# MLX81310EVB_BoardHolder.net
KiCad netlist of a schematic drawn in EAGLE
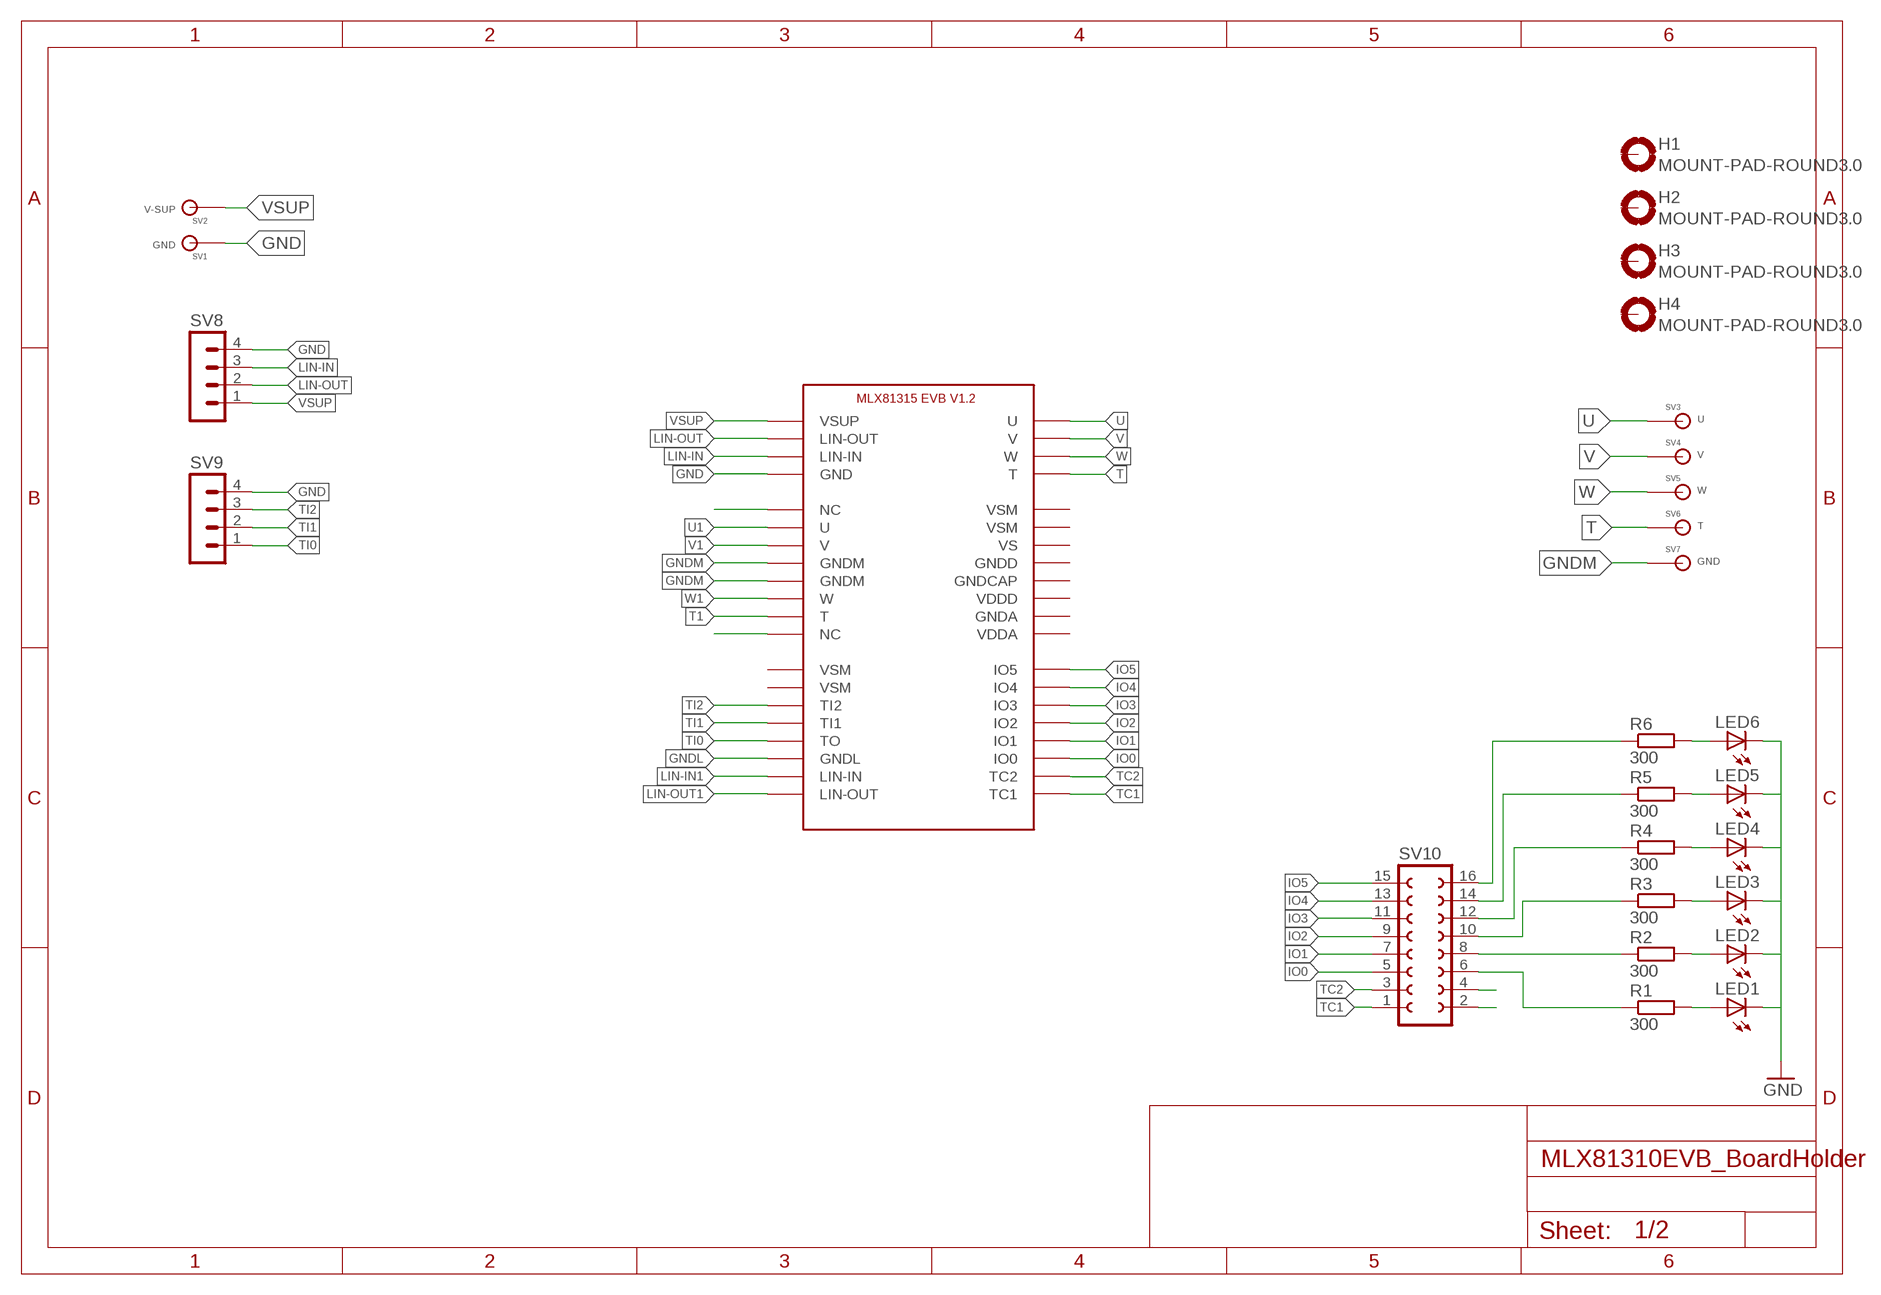
[diagram p0: schematic, sheet 1]
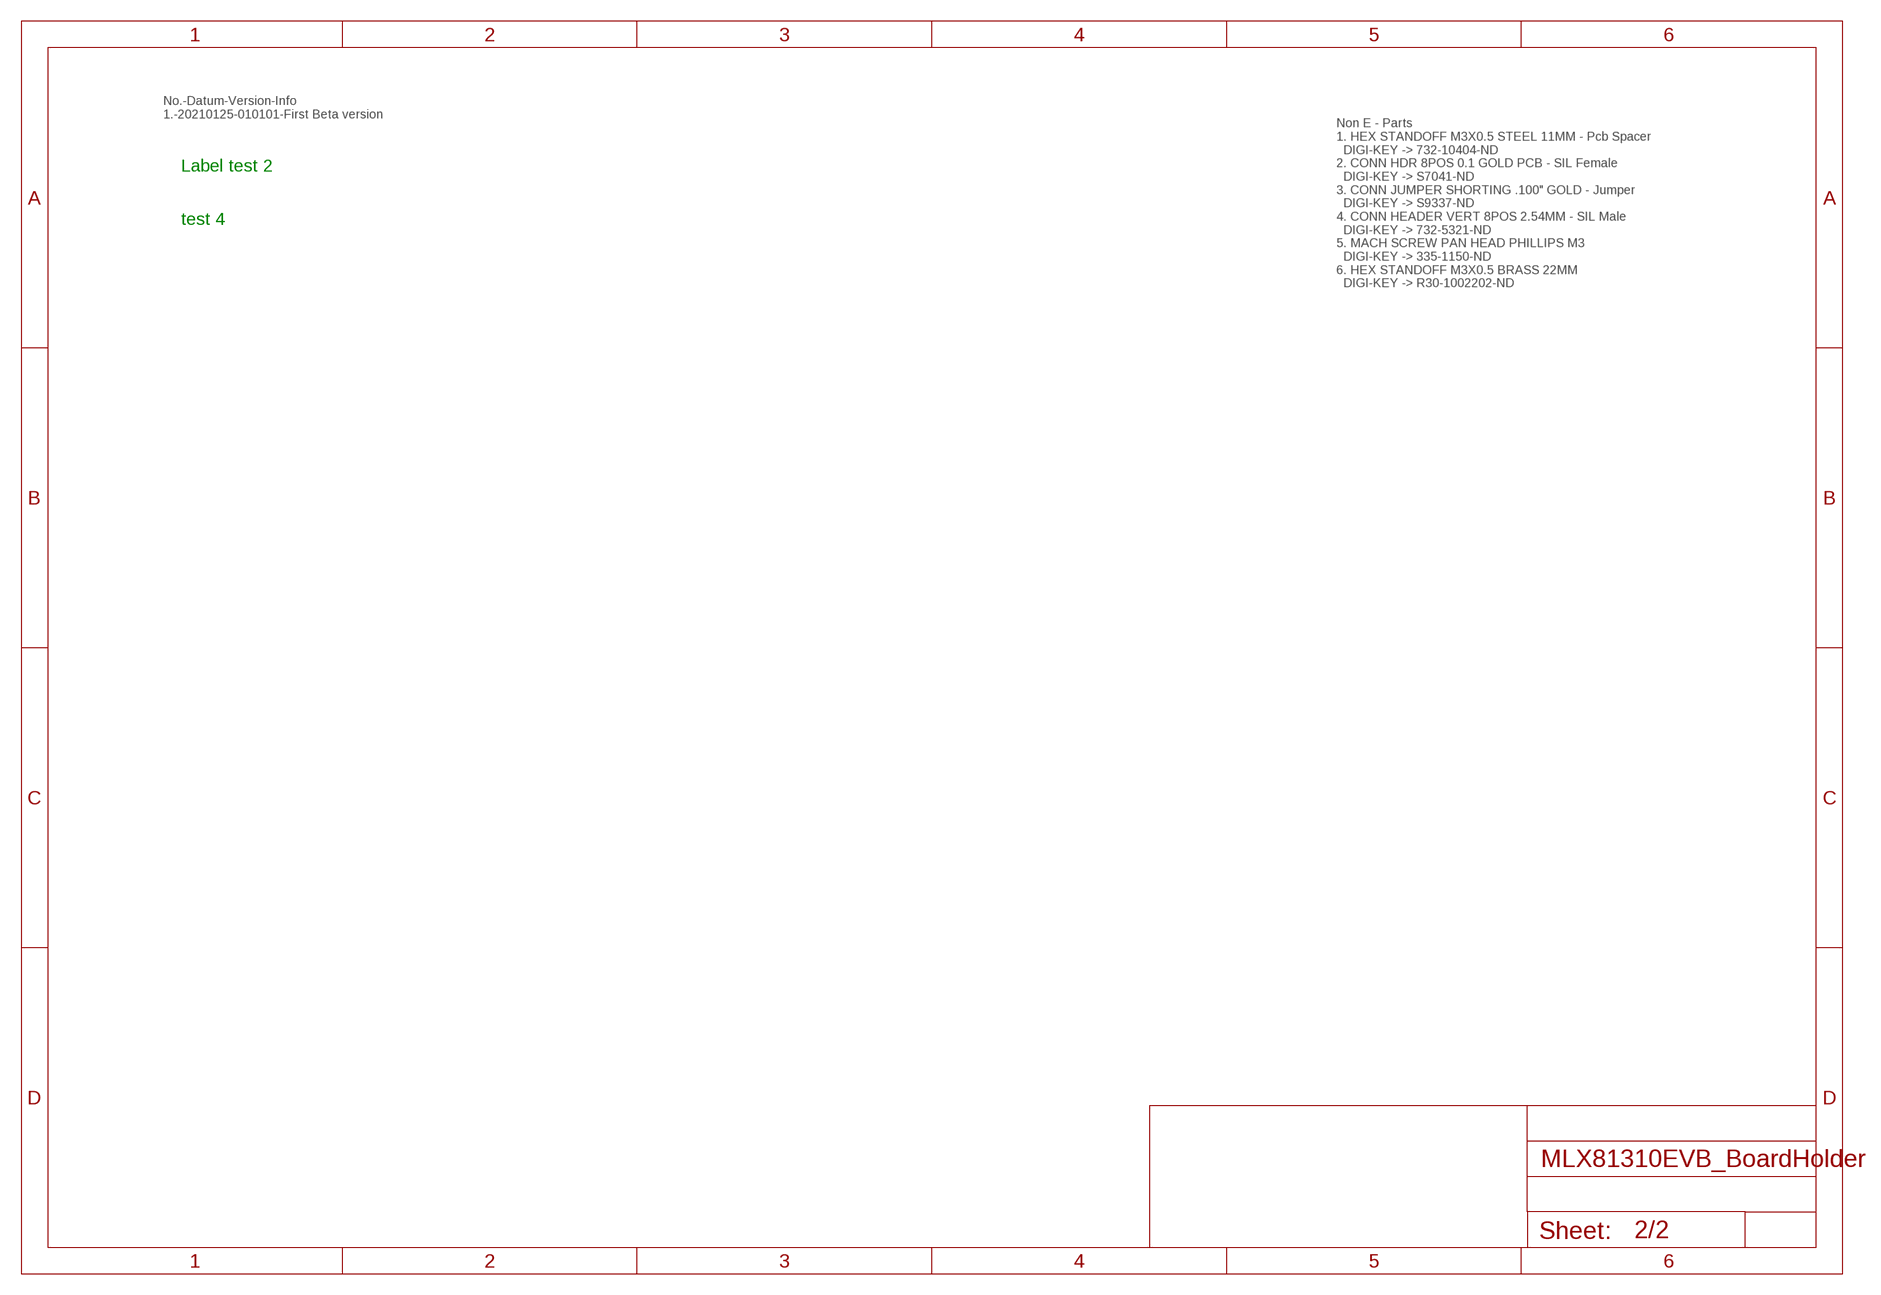
[diagram p1: schematic, sheet 2]

(export (version "E")
  (design (tool "Eeschema 10.0.6"))
  (components
    (comp (ref "B1")
      (value "MLX91315_EVB")
      (footprint "eagle-import:MLX81315EVB")
      (libsource (lib "eagle-import") (part "MLX91315_EVB"))
    )
    (comp (ref "H1")
      (value "MOUNT-PAD-ROUND3.0")
      (footprint "eagle-import:3,0-PAD")
      (libsource (lib "eagle-import") (part "MOUNT-PAD-ROUND3.0"))
    )
    (comp (ref "H2")
      (value "MOUNT-PAD-ROUND3.0")
      (footprint "eagle-import:3,0-PAD")
      (libsource (lib "eagle-import") (part "MOUNT-PAD-ROUND3.0"))
    )
    (comp (ref "H3")
      (value "MOUNT-PAD-ROUND3.0")
      (footprint "eagle-import:3,0-PAD")
      (libsource (lib "eagle-import") (part "MOUNT-PAD-ROUND3.0"))
    )
    (comp (ref "H4")
      (value "MOUNT-PAD-ROUND3.0")
      (footprint "eagle-import:3,0-PAD")
      (libsource (lib "eagle-import") (part "MOUNT-PAD-ROUND3.0"))
    )
    (comp (ref "LED1")
      (value "LEDCHIPLED_0805")
      (footprint "eagle-import:CHIPLED_0805")
      (libsource (lib "eagle-import") (part "LEDCHIPLED_0805"))
    )
    (comp (ref "LED2")
      (value "LEDCHIPLED_0805")
      (footprint "eagle-import:CHIPLED_0805")
      (libsource (lib "eagle-import") (part "LEDCHIPLED_0805"))
    )
    (comp (ref "LED3")
      (value "LEDCHIPLED_0805")
      (footprint "eagle-import:CHIPLED_0805")
      (libsource (lib "eagle-import") (part "LEDCHIPLED_0805"))
    )
    (comp (ref "LED4")
      (value "LEDCHIPLED_0805")
      (footprint "eagle-import:CHIPLED_0805")
      (libsource (lib "eagle-import") (part "LEDCHIPLED_0805"))
    )
    (comp (ref "LED5")
      (value "LEDCHIPLED_0805")
      (footprint "eagle-import:CHIPLED_0805")
      (libsource (lib "eagle-import") (part "LEDCHIPLED_0805"))
    )
    (comp (ref "LED6")
      (value "LEDCHIPLED_0805")
      (footprint "eagle-import:CHIPLED_0805")
      (libsource (lib "eagle-import") (part "LEDCHIPLED_0805"))
    )
    (comp (ref "R1")
      (value "300")
      (footprint "eagle-import:M0805")
      (libsource (lib "eagle-import") (part "R-EU_M0805"))
    )
    (comp (ref "R2")
      (value "300")
      (footprint "eagle-import:M0805")
      (libsource (lib "eagle-import") (part "R-EU_M0805"))
    )
    (comp (ref "R3")
      (value "300")
      (footprint "eagle-import:M0805")
      (libsource (lib "eagle-import") (part "R-EU_M0805"))
    )
    (comp (ref "R4")
      (value "300")
      (footprint "eagle-import:M0805")
      (libsource (lib "eagle-import") (part "R-EU_M0805"))
    )
    (comp (ref "R5")
      (value "300")
      (footprint "eagle-import:M0805")
      (libsource (lib "eagle-import") (part "R-EU_M0805"))
    )
    (comp (ref "R6")
      (value "300")
      (footprint "eagle-import:M0805")
      (libsource (lib "eagle-import") (part "R-EU_M0805"))
    )
    (comp (ref "SV1")
      (value "GND")
      (footprint "eagle-import:BANANNA_CONNECTOR_SOLIDER_4MM")
      (libsource (lib "eagle-import") (part "BANANNA_CONNECTOR_SOLDER_4MM"))
    )
    (comp (ref "SV2")
      (value "V-SUP")
      (footprint "eagle-import:BANANNA_CONNECTOR_SOLIDER_4MM")
      (libsource (lib "eagle-import") (part "BANANNA_CONNECTOR_SOLDER_4MM"))
    )
    (comp (ref "SV3")
      (value "U")
      (footprint "eagle-import:BANANNA_CONNECTOR_SOLIDER_4MM")
      (libsource (lib "eagle-import") (part "BANANNA_CONNECTOR_SOLDER_4MM"))
    )
    (comp (ref "SV4")
      (value "V")
      (footprint "eagle-import:BANANNA_CONNECTOR_SOLIDER_4MM")
      (libsource (lib "eagle-import") (part "BANANNA_CONNECTOR_SOLDER_4MM"))
    )
    (comp (ref "SV5")
      (value "W")
      (footprint "eagle-import:BANANNA_CONNECTOR_SOLIDER_4MM")
      (libsource (lib "eagle-import") (part "BANANNA_CONNECTOR_SOLDER_4MM"))
    )
    (comp (ref "SV6")
      (value "T")
      (footprint "eagle-import:BANANNA_CONNECTOR_SOLIDER_4MM")
      (libsource (lib "eagle-import") (part "BANANNA_CONNECTOR_SOLDER_4MM"))
    )
    (comp (ref "SV7")
      (value "GND")
      (footprint "eagle-import:BANANNA_CONNECTOR_SOLIDER_4MM")
      (libsource (lib "eagle-import") (part "BANANNA_CONNECTOR_SOLDER_4MM"))
    )
    (comp (ref "SV8")
      (value "MA04-1")
      (footprint "eagle-import:MA04-1")
      (libsource (lib "eagle-import") (part "MA04-1"))
    )
    (comp (ref "SV9")
      (value "MA04-1")
      (footprint "eagle-import:MA04-1")
      (libsource (lib "eagle-import") (part "MA04-1"))
    )
    (comp (ref "SV10")
      (value "FE08-2")
      (footprint "eagle-import:FE08-2")
      (libsource (lib "eagle-import") (part "FE08-2"))
    )
  )
  (nets
    (net (code "1") (name "GND") (class "Default")
      (node (ref "B1") (pin "GND@1") (pinfunction "GND_GND@1") (pintype "bidirectional"))
      (node (ref "LED1") (pin "C") (pinfunction "C_C") (pintype "passive"))
      (node (ref "LED2") (pin "C") (pinfunction "C_C") (pintype "passive"))
      (node (ref "LED3") (pin "C") (pinfunction "C_C") (pintype "passive"))
      (node (ref "LED4") (pin "C") (pinfunction "C_C") (pintype "passive"))
      (node (ref "LED5") (pin "C") (pinfunction "C_C") (pintype "passive"))
      (node (ref "LED6") (pin "C") (pinfunction "C_C") (pintype "passive"))
      (node (ref "SV1") (pin "P$1") (pinfunction "P$1_P$1") (pintype "bidirectional"))
      (node (ref "SV8") (pin "4") (pinfunction "4_4") (pintype "passive"))
      (node (ref "SV9") (pin "4") (pinfunction "4_4") (pintype "passive"))
    )
    (net (code "2") (name "GNDL") (class "Default")
      (node (ref "B1") (pin "GNDL") (pinfunction "GNDL_GNDL") (pintype "bidirectional"))
    )
    (net (code "3") (name "GNDM") (class "Default")
      (node (ref "B1") (pin "GNDM@1") (pinfunction "GNDM_GNDM@1") (pintype "bidirectional"))
      (node (ref "B1") (pin "GNDM@2") (pinfunction "GNDM_GNDM@2") (pintype "bidirectional"))
      (node (ref "SV7") (pin "P$1") (pinfunction "P$1_P$1") (pintype "bidirectional"))
    )
    (net (code "4") (name "IO0") (class "Default")
      (node (ref "B1") (pin "IO0") (pinfunction "IO0_IO0") (pintype "bidirectional"))
      (node (ref "SV10") (pin "5") (pinfunction "5_5") (pintype "passive"))
    )
    (net (code "5") (name "IO1") (class "Default")
      (node (ref "B1") (pin "IO1") (pinfunction "IO1_IO1") (pintype "bidirectional"))
      (node (ref "SV10") (pin "7") (pinfunction "7_7") (pintype "passive"))
    )
    (net (code "6") (name "IO2") (class "Default")
      (node (ref "B1") (pin "IO2") (pinfunction "IO2_IO2") (pintype "bidirectional"))
      (node (ref "SV10") (pin "9") (pinfunction "9_9") (pintype "passive"))
    )
    (net (code "7") (name "IO3") (class "Default")
      (node (ref "B1") (pin "IO3") (pinfunction "IO3_IO3") (pintype "bidirectional"))
      (node (ref "SV10") (pin "11") (pinfunction "11_11") (pintype "passive"))
    )
    (net (code "8") (name "IO4") (class "Default")
      (node (ref "B1") (pin "IO4") (pinfunction "IO4_IO4") (pintype "bidirectional"))
      (node (ref "SV10") (pin "13") (pinfunction "13_13") (pintype "passive"))
    )
    (net (code "9") (name "IO5") (class "Default")
      (node (ref "B1") (pin "IO5") (pinfunction "IO5_IO5") (pintype "bidirectional"))
      (node (ref "SV10") (pin "15") (pinfunction "15_15") (pintype "passive"))
    )
    (net (code "10") (name "LIN-IN") (class "Default")
      (node (ref "B1") (pin "LIN-IN@1") (pinfunction "LIN-IN_LIN-IN@1") (pintype "bidirectional"))
      (node (ref "SV8") (pin "3") (pinfunction "3_3") (pintype "passive"))
    )
    (net (code "11") (name "LIN-IN1") (class "Default")
      (node (ref "B1") (pin "LIN-IN@2") (pinfunction "LIN-IN_LIN-IN@2") (pintype "bidirectional"))
    )
    (net (code "12") (name "LIN-OUT") (class "Default")
      (node (ref "B1") (pin "LIN-OUT@1") (pinfunction "LIN-OUT_LIN-OUT@1") (pintype "bidirectional"))
      (node (ref "SV8") (pin "2") (pinfunction "2_2") (pintype "passive"))
    )
    (net (code "13") (name "LIN-OUT1") (class "Default")
      (node (ref "B1") (pin "LIN-OUT@2") (pinfunction "LIN-OUT_LIN-OUT@2") (pintype "bidirectional"))
    )
    (net (code "14") (name "Net-(LED1-PadA)") (class "Default")
      (node (ref "LED1") (pin "A") (pinfunction "A_A") (pintype "passive"))
      (node (ref "R1") (pin "2") (pinfunction "2_2") (pintype "passive"))
    )
    (net (code "15") (name "Net-(LED2-PadA)") (class "Default")
      (node (ref "LED2") (pin "A") (pinfunction "A_A") (pintype "passive"))
      (node (ref "R2") (pin "2") (pinfunction "2_2") (pintype "passive"))
    )
    (net (code "16") (name "Net-(LED3-PadA)") (class "Default")
      (node (ref "LED3") (pin "A") (pinfunction "A_A") (pintype "passive"))
      (node (ref "R3") (pin "2") (pinfunction "2_2") (pintype "passive"))
    )
    (net (code "17") (name "Net-(LED4-PadA)") (class "Default")
      (node (ref "LED4") (pin "A") (pinfunction "A_A") (pintype "passive"))
      (node (ref "R4") (pin "2") (pinfunction "2_2") (pintype "passive"))
    )
    (net (code "18") (name "Net-(LED5-PadA)") (class "Default")
      (node (ref "LED5") (pin "A") (pinfunction "A_A") (pintype "passive"))
      (node (ref "R5") (pin "2") (pinfunction "2_2") (pintype "passive"))
    )
    (net (code "19") (name "Net-(LED6-PadA)") (class "Default")
      (node (ref "LED6") (pin "A") (pinfunction "A_A") (pintype "passive"))
      (node (ref "R6") (pin "2") (pinfunction "2_2") (pintype "passive"))
    )
    (net (code "20") (name "Net-(R1-Pad1)") (class "Default")
      (node (ref "R1") (pin "1") (pinfunction "1_1") (pintype "passive"))
      (node (ref "SV10") (pin "6") (pinfunction "6_6") (pintype "passive"))
    )
    (net (code "21") (name "Net-(R2-Pad1)") (class "Default")
      (node (ref "R2") (pin "1") (pinfunction "1_1") (pintype "passive"))
      (node (ref "SV10") (pin "8") (pinfunction "8_8") (pintype "passive"))
    )
    (net (code "22") (name "Net-(R3-Pad1)") (class "Default")
      (node (ref "R3") (pin "1") (pinfunction "1_1") (pintype "passive"))
      (node (ref "SV10") (pin "10") (pinfunction "10_10") (pintype "passive"))
    )
    (net (code "23") (name "Net-(R4-Pad1)") (class "Default")
      (node (ref "R4") (pin "1") (pinfunction "1_1") (pintype "passive"))
      (node (ref "SV10") (pin "12") (pinfunction "12_12") (pintype "passive"))
    )
    (net (code "24") (name "Net-(R5-Pad1)") (class "Default")
      (node (ref "R5") (pin "1") (pinfunction "1_1") (pintype "passive"))
      (node (ref "SV10") (pin "14") (pinfunction "14_14") (pintype "passive"))
    )
    (net (code "25") (name "Net-(R6-Pad1)") (class "Default")
      (node (ref "R6") (pin "1") (pinfunction "1_1") (pintype "passive"))
      (node (ref "SV10") (pin "16") (pinfunction "16_16") (pintype "passive"))
    )
    (net (code "26") (name "T") (class "Default")
      (node (ref "B1") (pin "T@1") (pinfunction "T_T@1") (pintype "bidirectional"))
      (node (ref "SV6") (pin "P$1") (pinfunction "P$1_P$1") (pintype "bidirectional"))
    )
    (net (code "27") (name "T1") (class "Default")
      (node (ref "B1") (pin "T@2") (pinfunction "T_T@2") (pintype "bidirectional"))
    )
    (net (code "28") (name "TC1") (class "Default")
      (node (ref "B1") (pin "TC1") (pinfunction "TC1_TC1") (pintype "bidirectional"))
      (node (ref "SV10") (pin "1") (pinfunction "1_1") (pintype "passive"))
      (node (ref "SV10") (pin "2") (pinfunction "2_2") (pintype "passive"))
    )
    (net (code "29") (name "TC2") (class "Default")
      (node (ref "B1") (pin "TC2") (pinfunction "TC2_TC2") (pintype "bidirectional"))
      (node (ref "SV10") (pin "3") (pinfunction "3_3") (pintype "passive"))
      (node (ref "SV10") (pin "4") (pinfunction "4_4") (pintype "passive"))
    )
    (net (code "30") (name "TI0") (class "Default")
      (node (ref "B1") (pin "T0") (pinfunction "TO_T0") (pintype "bidirectional"))
      (node (ref "SV9") (pin "1") (pinfunction "1_1") (pintype "passive"))
    )
    (net (code "31") (name "TI1") (class "Default")
      (node (ref "B1") (pin "TI1") (pinfunction "TI1_TI1") (pintype "bidirectional"))
      (node (ref "SV9") (pin "2") (pinfunction "2_2") (pintype "passive"))
    )
    (net (code "32") (name "TI2") (class "Default")
      (node (ref "B1") (pin "TI2") (pinfunction "TI2_TI2") (pintype "bidirectional"))
      (node (ref "SV9") (pin "3") (pinfunction "3_3") (pintype "passive"))
    )
    (net (code "33") (name "U") (class "Default")
      (node (ref "B1") (pin "U@1") (pinfunction "U_U@1") (pintype "bidirectional"))
      (node (ref "SV3") (pin "P$1") (pinfunction "P$1_P$1") (pintype "bidirectional"))
    )
    (net (code "34") (name "U1") (class "Default")
      (node (ref "B1") (pin "U@2") (pinfunction "U_U@2") (pintype "bidirectional"))
    )
    (net (code "35") (name "V") (class "Default")
      (node (ref "B1") (pin "V@1") (pinfunction "V_V@1") (pintype "bidirectional"))
      (node (ref "SV4") (pin "P$1") (pinfunction "P$1_P$1") (pintype "bidirectional"))
    )
    (net (code "36") (name "V1") (class "Default")
      (node (ref "B1") (pin "V@2") (pinfunction "V_V@2") (pintype "bidirectional"))
    )
    (net (code "37") (name "VSUP") (class "Default")
      (node (ref "B1") (pin "VSUP") (pinfunction "VSUP_VSUP") (pintype "bidirectional"))
      (node (ref "SV2") (pin "P$1") (pinfunction "P$1_P$1") (pintype "bidirectional"))
      (node (ref "SV8") (pin "1") (pinfunction "1_1") (pintype "passive"))
    )
    (net (code "38") (name "W") (class "Default")
      (node (ref "B1") (pin "W@1") (pinfunction "W_W@1") (pintype "bidirectional"))
      (node (ref "SV5") (pin "P$1") (pinfunction "P$1_P$1") (pintype "bidirectional"))
    )
    (net (code "39") (name "W1") (class "Default")
      (node (ref "B1") (pin "W@2") (pinfunction "W_W@2") (pintype "bidirectional"))
    )
    (net (code "40") (name "unconnected-(B1-NC-PadNC$1)") (class "Default")
      (node (ref "B1") (pin "NC$1") (pinfunction "NC_NC$1") (pintype "bidirectional"))
    )
    (net (code "41") (name "unconnected-(B1-NC-PadNC@8)") (class "Default")
      (node (ref "B1") (pin "NC@8") (pinfunction "NC_NC@8") (pintype "bidirectional"))
    )
    (net (code "42") (name "unconnected-(B1-PadGNDA)") (class "Default")
      (node (ref "B1") (pin "GNDA") (pinfunction "GNDA_GNDA") (pintype "bidirectional"))
    )
    (net (code "43") (name "unconnected-(B1-PadGNDCAP)") (class "Default")
      (node (ref "B1") (pin "GNDCAP") (pinfunction "GNDCAP_GNDCAP") (pintype "bidirectional"))
    )
    (net (code "44") (name "unconnected-(B1-PadGNDD)") (class "Default")
      (node (ref "B1") (pin "GNDD") (pinfunction "GNDD_GNDD") (pintype "bidirectional"))
    )
    (net (code "45") (name "unconnected-(B1-PadVDDA)") (class "Default")
      (node (ref "B1") (pin "VDDA") (pinfunction "VDDA_VDDA") (pintype "bidirectional"))
    )
    (net (code "46") (name "unconnected-(B1-PadVDDD)") (class "Default")
      (node (ref "B1") (pin "VDDD") (pinfunction "VDDD_VDDD") (pintype "bidirectional"))
    )
    (net (code "47") (name "unconnected-(B1-PadVS)") (class "Default")
      (node (ref "B1") (pin "VS") (pinfunction "VS_VS") (pintype "bidirectional"))
    )
    (net (code "48") (name "unconnected-(B1-VSM-PadVSM$1)") (class "Default")
      (node (ref "B1") (pin "VSM$1") (pinfunction "VSM_VSM$1") (pintype "bidirectional"))
    )
    (net (code "49") (name "unconnected-(B1-VSM-PadVSM$2)") (class "Default")
      (node (ref "B1") (pin "VSM$2") (pinfunction "VSM_VSM$2") (pintype "bidirectional"))
    )
    (net (code "50") (name "unconnected-(B1-VSM-PadVSM@1)") (class "Default")
      (node (ref "B1") (pin "VSM@1") (pinfunction "VSM_VSM@1") (pintype "bidirectional"))
    )
    (net (code "51") (name "unconnected-(B1-VSM-PadVSM@2)") (class "Default")
      (node (ref "B1") (pin "VSM@2") (pinfunction "VSM_VSM@2") (pintype "bidirectional"))
    )
    (net (code "52") (name "unconnected-(H1-MOUNT-PadB3,0)") (class "Default")
      (node (ref "H1") (pin "B3,0") (pinfunction "MOUNT_B3,0") (pintype "passive"))
    )
    (net (code "53") (name "unconnected-(H2-MOUNT-PadB3,0)") (class "Default")
      (node (ref "H2") (pin "B3,0") (pinfunction "MOUNT_B3,0") (pintype "passive"))
    )
    (net (code "54") (name "unconnected-(H3-MOUNT-PadB3,0)") (class "Default")
      (node (ref "H3") (pin "B3,0") (pinfunction "MOUNT_B3,0") (pintype "passive"))
    )
    (net (code "55") (name "unconnected-(H4-MOUNT-PadB3,0)") (class "Default")
      (node (ref "H4") (pin "B3,0") (pinfunction "MOUNT_B3,0") (pintype "passive"))
    )
  )
)
